# M149C.net
KiCad netlist of a schematic drawn in EAGLE
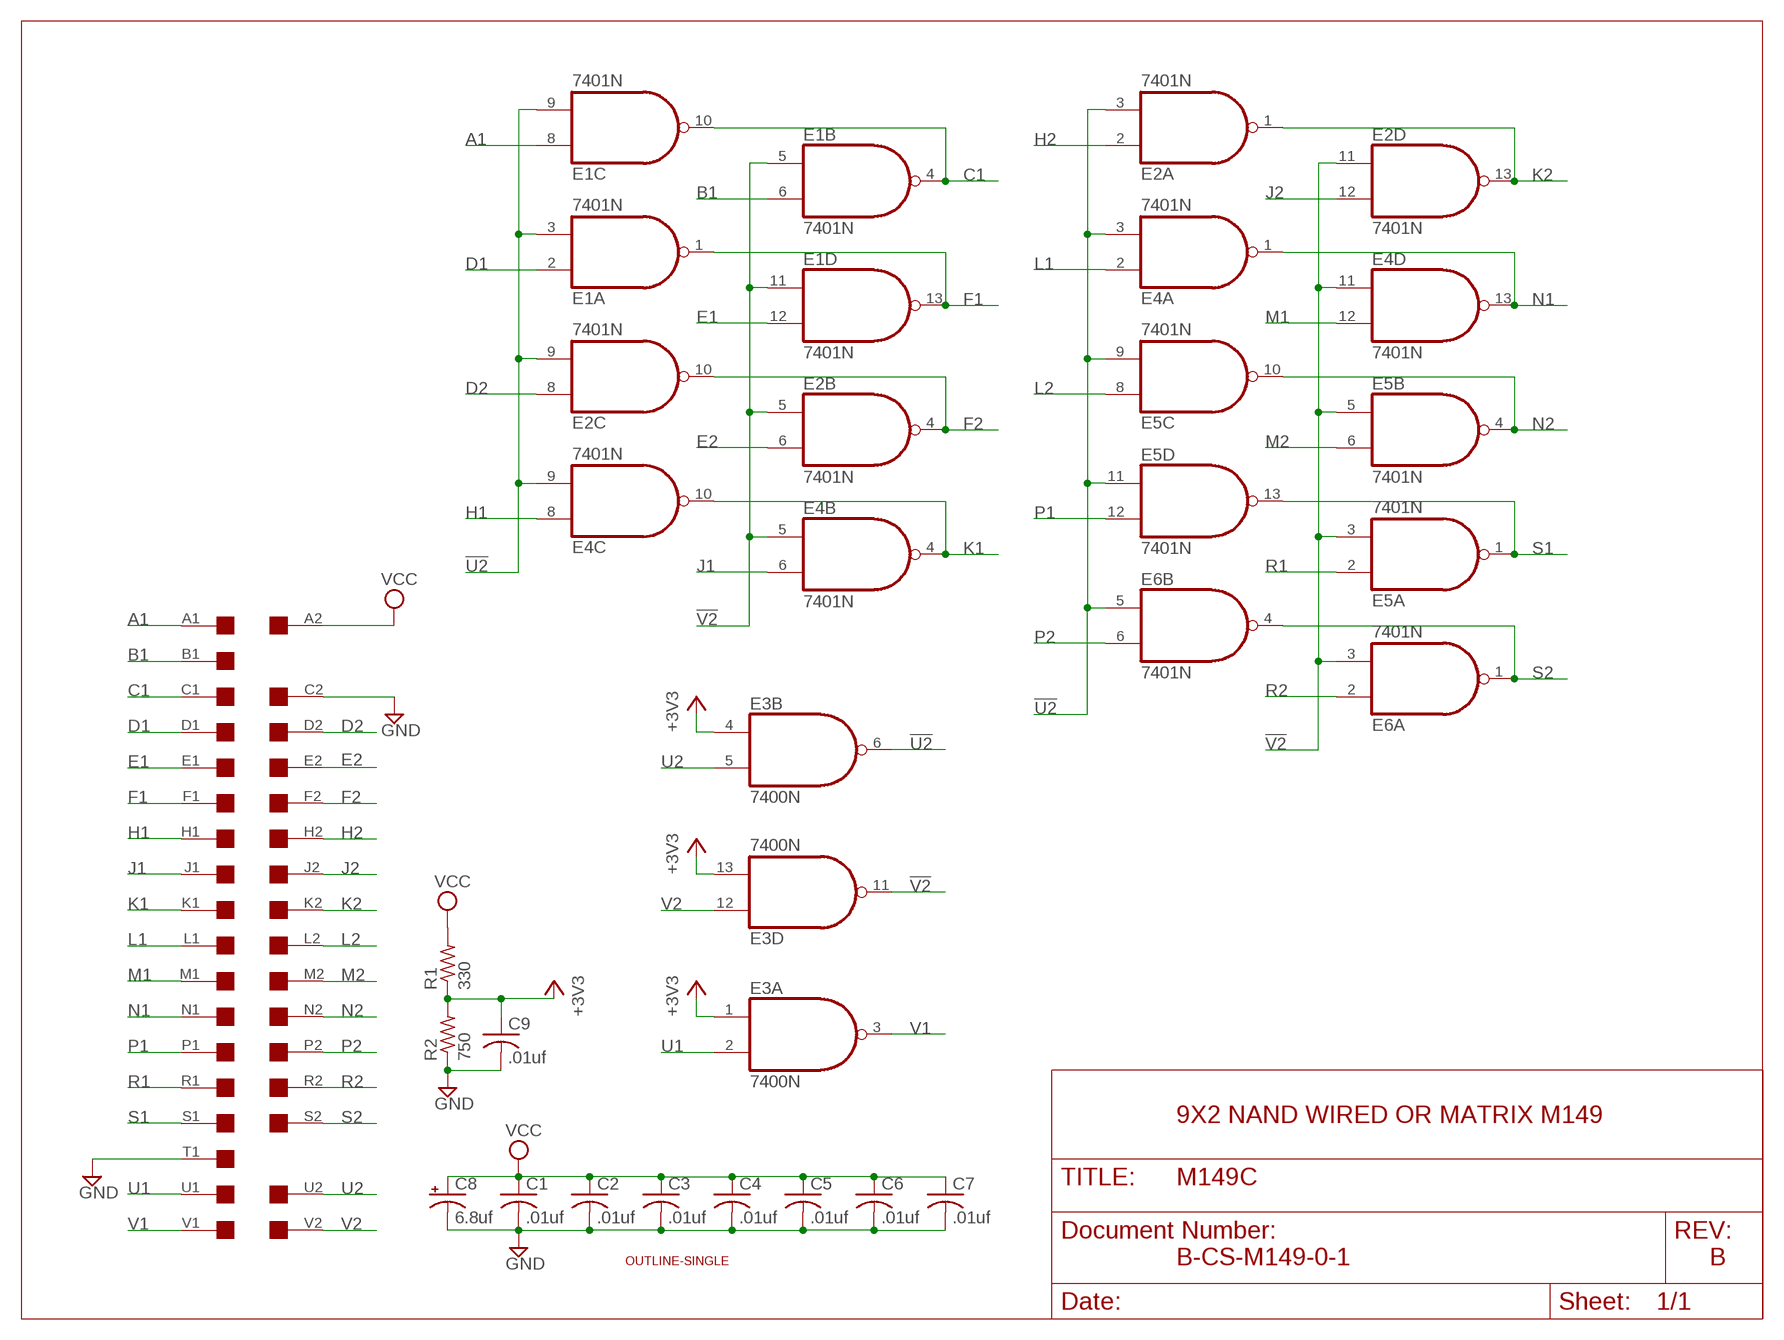
[diagram p0: schematic, sheet 1]

(export (version "E")
  (design (tool "Eeschema 10.0.6"))
  (components
    (comp (ref "C1")
      (value ".01uf")
      (footprint "eagle-import:C050-025X075")
      (libsource (lib "eagle-import") (part "C-US050-025X075"))
    )
    (comp (ref "C2")
      (value ".01uf")
      (footprint "eagle-import:C050-025X075")
      (libsource (lib "eagle-import") (part "C-US050-025X075"))
    )
    (comp (ref "C3")
      (value ".01uf")
      (footprint "eagle-import:C050-025X075")
      (libsource (lib "eagle-import") (part "C-US050-025X075"))
    )
    (comp (ref "C4")
      (value ".01uf")
      (footprint "eagle-import:C050-025X075")
      (libsource (lib "eagle-import") (part "C-US050-025X075"))
    )
    (comp (ref "C5")
      (value ".01uf")
      (footprint "eagle-import:C050-025X075")
      (libsource (lib "eagle-import") (part "C-US050-025X075"))
    )
    (comp (ref "C6")
      (value ".01uf")
      (footprint "eagle-import:C050-025X075")
      (libsource (lib "eagle-import") (part "C-US050-025X075"))
    )
    (comp (ref "C7")
      (value ".01uf")
      (footprint "eagle-import:C050-025X075")
      (libsource (lib "eagle-import") (part "C-US050-025X075"))
    )
    (comp (ref "C8")
      (value "6.8uf")
      (footprint "eagle-import:E15-5")
      (libsource (lib "eagle-import") (part "CPOL-USE15-5AXIAL"))
    )
    (comp (ref "C9")
      (value ".01uf")
      (footprint "eagle-import:C050-025X075")
      (libsource (lib "eagle-import") (part "C-US050-025X075"))
    )
    (comp (ref "E1")
      (value "7401N")
      (footprint "eagle-import:DIL14")
      (libsource (lib "eagle-import") (part "7401NLS"))
    )
    (comp (ref "E2")
      (value "7401N")
      (footprint "eagle-import:DIL14")
      (libsource (lib "eagle-import") (part "7401NLS"))
    )
    (comp (ref "E3")
      (value "7400N")
      (footprint "eagle-import:DIL14")
      (libsource (lib "eagle-import") (part "7400N"))
    )
    (comp (ref "E4")
      (value "7401N")
      (footprint "eagle-import:DIL14")
      (libsource (lib "eagle-import") (part "7401NLS"))
    )
    (comp (ref "E5")
      (value "7401N")
      (footprint "eagle-import:DIL14")
      (libsource (lib "eagle-import") (part "7401NLS"))
    )
    (comp (ref "E6")
      (value "7401N")
      (footprint "eagle-import:DIL14")
      (libsource (lib "eagle-import") (part "7401NLS"))
    )
    (comp (ref "R1")
      (value "330")
      (footprint "eagle-import:0207_10")
      (libsource (lib "eagle-import") (part "R-US_0207/10"))
    )
    (comp (ref "R2")
      (value "750")
      (footprint "eagle-import:0207_10")
      (libsource (lib "eagle-import") (part "R-US_0207/10"))
    )
    (comp (ref "U$1")
      (value "SINGLE")
      (footprint "eagle-import:EDGE-CON2")
      (libsource (lib "eagle-import") (part "SINGLE"))
    )
    (comp (ref "U$4")
      (value "OUTLINE-SINGLE")
      (footprint "eagle-import:SINGLE")
      (libsource (lib "eagle-import") (part "OUTLINE-SINGLE"))
    )
  )
  (nets
    (net (code "1") (name "+3V3") (class "Default")
      (node (ref "C9") (pin "1") (pinfunction "1_1") (pintype "passive"))
      (node (ref "E3") (pin "1") (pinfunction "I0_1") (pintype "input"))
      (node (ref "E3") (pin "13") (pinfunction "I1_13") (pintype "input"))
      (node (ref "E3") (pin "4") (pinfunction "I0_4") (pintype "input"))
      (node (ref "R1") (pin "1") (pinfunction "1_1") (pintype "passive"))
      (node (ref "R2") (pin "2") (pinfunction "2_2") (pintype "passive"))
    )
    (net (code "2") (name "/A1") (class "Default")
      (node (ref "E1") (pin "8") (pinfunction "I0_8") (pintype "input"))
      (node (ref "U$1") (pin "A1") (pinfunction "1_A1") (pintype "bidirectional"))
    )
    (net (code "3") (name "/B1") (class "Default")
      (node (ref "E1") (pin "6") (pinfunction "I1_6") (pintype "input"))
      (node (ref "U$1") (pin "B1") (pinfunction "1_B1") (pintype "bidirectional"))
    )
    (net (code "4") (name "/C1") (class "Default")
      (node (ref "E1") (pin "10") (pinfunction "O_10") (pintype "open_collector"))
      (node (ref "E1") (pin "4") (pinfunction "O_4") (pintype "open_collector"))
      (node (ref "U$1") (pin "C1") (pinfunction "1_C1") (pintype "bidirectional"))
    )
    (net (code "5") (name "/D1") (class "Default")
      (node (ref "E1") (pin "2") (pinfunction "I0_2") (pintype "input"))
      (node (ref "U$1") (pin "D1") (pinfunction "1_D1") (pintype "bidirectional"))
    )
    (net (code "6") (name "/D2") (class "Default")
      (node (ref "E2") (pin "8") (pinfunction "I0_8") (pintype "input"))
      (node (ref "U$1") (pin "D2") (pinfunction "1_D2") (pintype "bidirectional"))
    )
    (net (code "7") (name "/E1") (class "Default")
      (node (ref "E1") (pin "12") (pinfunction "I1_12") (pintype "input"))
      (node (ref "U$1") (pin "E1") (pinfunction "1_E1") (pintype "bidirectional"))
    )
    (net (code "8") (name "/E2") (class "Default")
      (node (ref "E2") (pin "6") (pinfunction "I1_6") (pintype "input"))
      (node (ref "U$1") (pin "E2") (pinfunction "1_E2") (pintype "bidirectional"))
    )
    (net (code "9") (name "/F1") (class "Default")
      (node (ref "E1") (pin "1") (pinfunction "O_1") (pintype "open_collector"))
      (node (ref "E1") (pin "13") (pinfunction "O_13") (pintype "open_collector"))
      (node (ref "U$1") (pin "F1") (pinfunction "1_F1") (pintype "bidirectional"))
    )
    (net (code "10") (name "/F2") (class "Default")
      (node (ref "E2") (pin "10") (pinfunction "O_10") (pintype "open_collector"))
      (node (ref "E2") (pin "4") (pinfunction "O_4") (pintype "open_collector"))
      (node (ref "U$1") (pin "F2") (pinfunction "1_F2") (pintype "bidirectional"))
    )
    (net (code "11") (name "/H1") (class "Default")
      (node (ref "E4") (pin "8") (pinfunction "I0_8") (pintype "input"))
      (node (ref "U$1") (pin "H1") (pinfunction "1_H1") (pintype "bidirectional"))
    )
    (net (code "12") (name "/H2") (class "Default")
      (node (ref "E2") (pin "2") (pinfunction "I0_2") (pintype "input"))
      (node (ref "U$1") (pin "H2") (pinfunction "1_H2") (pintype "bidirectional"))
    )
    (net (code "13") (name "/J1") (class "Default")
      (node (ref "E4") (pin "6") (pinfunction "I1_6") (pintype "input"))
      (node (ref "U$1") (pin "J1") (pinfunction "1_J1") (pintype "bidirectional"))
    )
    (net (code "14") (name "/J2") (class "Default")
      (node (ref "E2") (pin "12") (pinfunction "I1_12") (pintype "input"))
      (node (ref "U$1") (pin "J2") (pinfunction "1_J2") (pintype "bidirectional"))
    )
    (net (code "15") (name "/K1") (class "Default")
      (node (ref "E4") (pin "10") (pinfunction "O_10") (pintype "open_collector"))
      (node (ref "E4") (pin "4") (pinfunction "O_4") (pintype "open_collector"))
      (node (ref "U$1") (pin "K1") (pinfunction "1_K1") (pintype "bidirectional"))
    )
    (net (code "16") (name "/K2") (class "Default")
      (node (ref "E2") (pin "1") (pinfunction "O_1") (pintype "open_collector"))
      (node (ref "E2") (pin "13") (pinfunction "O_13") (pintype "open_collector"))
      (node (ref "U$1") (pin "K2") (pinfunction "1_K2") (pintype "bidirectional"))
    )
    (net (code "17") (name "/L1") (class "Default")
      (node (ref "E4") (pin "2") (pinfunction "I0_2") (pintype "input"))
      (node (ref "U$1") (pin "L1") (pinfunction "1_L1") (pintype "bidirectional"))
    )
    (net (code "18") (name "/L2") (class "Default")
      (node (ref "E5") (pin "8") (pinfunction "I0_8") (pintype "input"))
      (node (ref "U$1") (pin "L2") (pinfunction "1_L2") (pintype "bidirectional"))
    )
    (net (code "19") (name "/M1") (class "Default")
      (node (ref "E4") (pin "12") (pinfunction "I1_12") (pintype "input"))
      (node (ref "U$1") (pin "M1") (pinfunction "1_M1") (pintype "bidirectional"))
    )
    (net (code "20") (name "/M2") (class "Default")
      (node (ref "E5") (pin "6") (pinfunction "I1_6") (pintype "input"))
      (node (ref "U$1") (pin "M2") (pinfunction "1_M2") (pintype "bidirectional"))
    )
    (net (code "21") (name "/N1") (class "Default")
      (node (ref "E4") (pin "1") (pinfunction "O_1") (pintype "open_collector"))
      (node (ref "E4") (pin "13") (pinfunction "O_13") (pintype "open_collector"))
      (node (ref "U$1") (pin "N1") (pinfunction "1_N1") (pintype "bidirectional"))
    )
    (net (code "22") (name "/N2") (class "Default")
      (node (ref "E5") (pin "10") (pinfunction "O_10") (pintype "open_collector"))
      (node (ref "E5") (pin "4") (pinfunction "O_4") (pintype "open_collector"))
      (node (ref "U$1") (pin "N2") (pinfunction "1_N2") (pintype "bidirectional"))
    )
    (net (code "23") (name "/P1") (class "Default")
      (node (ref "E5") (pin "12") (pinfunction "I1_12") (pintype "input"))
      (node (ref "U$1") (pin "P1") (pinfunction "1_P1") (pintype "bidirectional"))
    )
    (net (code "24") (name "/P2") (class "Default")
      (node (ref "E6") (pin "6") (pinfunction "I1_6") (pintype "input"))
      (node (ref "U$1") (pin "P2") (pinfunction "1_P2") (pintype "bidirectional"))
    )
    (net (code "25") (name "/R1") (class "Default")
      (node (ref "E5") (pin "2") (pinfunction "I0_2") (pintype "input"))
      (node (ref "U$1") (pin "R1") (pinfunction "1_R1") (pintype "bidirectional"))
    )
    (net (code "26") (name "/R2") (class "Default")
      (node (ref "E6") (pin "2") (pinfunction "I0_2") (pintype "input"))
      (node (ref "U$1") (pin "R2") (pinfunction "1_R2") (pintype "bidirectional"))
    )
    (net (code "27") (name "/S1") (class "Default")
      (node (ref "E5") (pin "1") (pinfunction "O_1") (pintype "open_collector"))
      (node (ref "E5") (pin "13") (pinfunction "O_13") (pintype "open_collector"))
      (node (ref "U$1") (pin "S1") (pinfunction "1_S1") (pintype "bidirectional"))
    )
    (net (code "28") (name "/S2") (class "Default")
      (node (ref "E6") (pin "1") (pinfunction "O_1") (pintype "open_collector"))
      (node (ref "E6") (pin "4") (pinfunction "O_4") (pintype "open_collector"))
      (node (ref "U$1") (pin "S2") (pinfunction "1_S2") (pintype "bidirectional"))
    )
    (net (code "29") (name "/U1") (class "Default")
      (node (ref "E3") (pin "2") (pinfunction "I1_2") (pintype "input"))
      (node (ref "U$1") (pin "U1") (pinfunction "1_U1") (pintype "bidirectional"))
    )
    (net (code "30") (name "/U2") (class "Default")
      (node (ref "E3") (pin "5") (pinfunction "I1_5") (pintype "input"))
      (node (ref "U$1") (pin "U2") (pinfunction "1_U2") (pintype "bidirectional"))
    )
    (net (code "31") (name "/V1") (class "Default")
      (node (ref "E3") (pin "3") (pinfunction "O_3") (pintype "output"))
      (node (ref "U$1") (pin "V1") (pinfunction "1_V1") (pintype "bidirectional"))
    )
    (net (code "32") (name "/V2") (class "Default")
      (node (ref "E3") (pin "12") (pinfunction "I0_12") (pintype "input"))
      (node (ref "U$1") (pin "V2") (pinfunction "1_V2") (pintype "bidirectional"))
    )
    (net (code "33") (name "/~{U2}") (class "Default")
      (node (ref "E1") (pin "3") (pinfunction "I1_3") (pintype "input"))
      (node (ref "E1") (pin "9") (pinfunction "I1_9") (pintype "input"))
      (node (ref "E2") (pin "3") (pinfunction "I1_3") (pintype "input"))
      (node (ref "E2") (pin "9") (pinfunction "I1_9") (pintype "input"))
      (node (ref "E3") (pin "6") (pinfunction "O_6") (pintype "output"))
      (node (ref "E4") (pin "3") (pinfunction "I1_3") (pintype "input"))
      (node (ref "E4") (pin "9") (pinfunction "I1_9") (pintype "input"))
      (node (ref "E5") (pin "11") (pinfunction "I0_11") (pintype "input"))
      (node (ref "E5") (pin "9") (pinfunction "I1_9") (pintype "input"))
      (node (ref "E6") (pin "5") (pinfunction "I0_5") (pintype "input"))
    )
    (net (code "34") (name "/~{V2}") (class "Default")
      (node (ref "E1") (pin "11") (pinfunction "I0_11") (pintype "input"))
      (node (ref "E1") (pin "5") (pinfunction "I0_5") (pintype "input"))
      (node (ref "E2") (pin "11") (pinfunction "I0_11") (pintype "input"))
      (node (ref "E2") (pin "5") (pinfunction "I0_5") (pintype "input"))
      (node (ref "E3") (pin "11") (pinfunction "O_11") (pintype "output"))
      (node (ref "E4") (pin "11") (pinfunction "I0_11") (pintype "input"))
      (node (ref "E4") (pin "5") (pinfunction "I0_5") (pintype "input"))
      (node (ref "E5") (pin "3") (pinfunction "I1_3") (pintype "input"))
      (node (ref "E5") (pin "5") (pinfunction "I0_5") (pintype "input"))
      (node (ref "E6") (pin "3") (pinfunction "I1_3") (pintype "input"))
    )
    (net (code "35") (name "GND") (class "Default")
      (node (ref "C1") (pin "2") (pinfunction "2_2") (pintype "passive"))
      (node (ref "C2") (pin "2") (pinfunction "2_2") (pintype "passive"))
      (node (ref "C3") (pin "2") (pinfunction "2_2") (pintype "passive"))
      (node (ref "C4") (pin "2") (pinfunction "2_2") (pintype "passive"))
      (node (ref "C5") (pin "2") (pinfunction "2_2") (pintype "passive"))
      (node (ref "C6") (pin "2") (pinfunction "2_2") (pintype "passive"))
      (node (ref "C7") (pin "2") (pinfunction "2_2") (pintype "passive"))
      (node (ref "C8") (pin "-") (pinfunction "-_-") (pintype "passive"))
      (node (ref "C9") (pin "2") (pinfunction "2_2") (pintype "passive"))
      (node (ref "R2") (pin "1") (pinfunction "1_1") (pintype "passive"))
      (node (ref "U$1") (pin "C2") (pinfunction "1_C2") (pintype "bidirectional"))
      (node (ref "U$1") (pin "T1") (pinfunction "1_T1") (pintype "bidirectional"))
    )
    (net (code "36") (name "VCC") (class "Default")
      (node (ref "C1") (pin "1") (pinfunction "1_1") (pintype "passive"))
      (node (ref "C2") (pin "1") (pinfunction "1_1") (pintype "passive"))
      (node (ref "C3") (pin "1") (pinfunction "1_1") (pintype "passive"))
      (node (ref "C4") (pin "1") (pinfunction "1_1") (pintype "passive"))
      (node (ref "C5") (pin "1") (pinfunction "1_1") (pintype "passive"))
      (node (ref "C6") (pin "1") (pinfunction "1_1") (pintype "passive"))
      (node (ref "C7") (pin "1") (pinfunction "1_1") (pintype "passive"))
      (node (ref "C8") (pin "+") (pinfunction "+_+") (pintype "passive"))
      (node (ref "R1") (pin "2") (pinfunction "2_2") (pintype "passive"))
      (node (ref "U$1") (pin "A2") (pinfunction "1_A2") (pintype "bidirectional"))
    )
  )
)
